# WickedSwitch.net
KiCad netlist of a schematic drawn in EAGLE
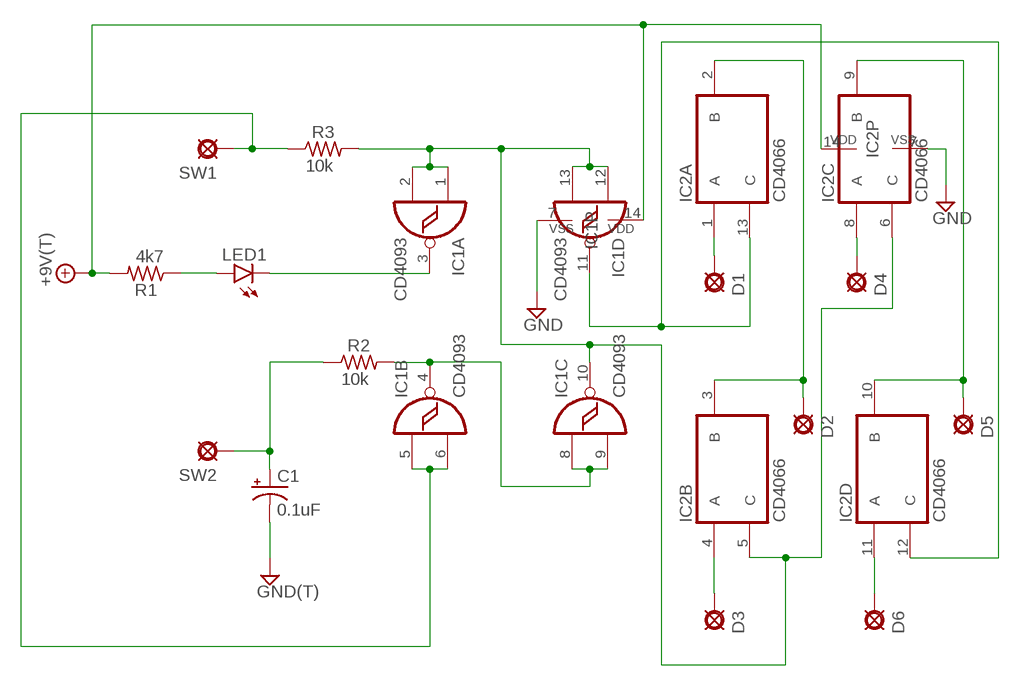
[diagram p0: schematic, sheet 1]

(export (version "E")
  (design (tool "Eeschema 10.0.6"))
  (components
    (comp (ref "+9V")
      (value "+9V(T)")
      (footprint "eagle-import:SQUARE")
      (libsource (lib "eagle-import") (part "+9V(T)"))
    )
    (comp (ref "C1")
      (value "0.1uF")
      (footprint "eagle-import:050_020_1")
      (libsource (lib "eagle-import") (part "0501"))
    )
    (comp (ref "D1")
      (value "1")
      (footprint "eagle-import:ROUND")
      (libsource (lib "eagle-import") (part "PADO"))
    )
    (comp (ref "D2")
      (value "1")
      (footprint "eagle-import:ROUND")
      (libsource (lib "eagle-import") (part "PADO"))
    )
    (comp (ref "D3")
      (value "1")
      (footprint "eagle-import:ROUND")
      (libsource (lib "eagle-import") (part "PADO"))
    )
    (comp (ref "D4")
      (value "1")
      (footprint "eagle-import:ROUND")
      (libsource (lib "eagle-import") (part "PADO"))
    )
    (comp (ref "D5")
      (value "1")
      (footprint "eagle-import:ROUND")
      (libsource (lib "eagle-import") (part "PADO"))
    )
    (comp (ref "D6")
      (value "1")
      (footprint "eagle-import:ROUND")
      (libsource (lib "eagle-import") (part "PADO"))
    )
    (comp (ref "GND")
      (value "GND(T)")
      (footprint "eagle-import:SQUARE")
      (libsource (lib "eagle-import") (part "GND(T)"))
    )
    (comp (ref "IC1")
      (value "CD4093")
      (footprint "eagle-import:DIL14")
      (libsource (lib "eagle-import") (part "4093N"))
    )
    (comp (ref "IC2")
      (value "CD4066")
      (footprint "eagle-import:DIL14")
      (libsource (lib "eagle-import") (part "4066N"))
    )
    (comp (ref "LED1")
      (value "LED3MM")
      (footprint "eagle-import:LED3MM")
      (libsource (lib "eagle-import") (part "LED3MM"))
    )
    (comp (ref "R1")
      (value "4k7")
      (footprint "eagle-import:R0207_3")
      (libsource (lib "eagle-import") (part "6MM.3"))
    )
    (comp (ref "R2")
      (value "10k")
      (footprint "eagle-import:R0207_3")
      (libsource (lib "eagle-import") (part "6MM.3"))
    )
    (comp (ref "R3")
      (value "10k")
      (footprint "eagle-import:R0207_3")
      (libsource (lib "eagle-import") (part "6MM.3"))
    )
    (comp (ref "SW1")
      (value "1")
      (footprint "eagle-import:ROUND")
      (libsource (lib "eagle-import") (part "PADO"))
    )
    (comp (ref "SW2")
      (value "1")
      (footprint "eagle-import:ROUND")
      (libsource (lib "eagle-import") (part "PADO"))
    )
  )
  (nets
    (net (code "1") (name "+9V(T)") (class "Default")
      (node (ref "+9V") (pin "1") (pinfunction "+9V_1") (pintype "power_in"))
      (node (ref "IC1") (pin "14") (pinfunction "VDD_14") (pintype "power_in"))
      (node (ref "IC2") (pin "14") (pinfunction "VDD_14") (pintype "power_in"))
      (node (ref "R1") (pin "2") (pinfunction "2_2") (pintype "passive"))
    )
    (net (code "2") (name "GND") (class "Default")
      (node (ref "C1") (pin "-") (pinfunction "-_-") (pintype "passive"))
      (node (ref "GND") (pin "1") (pinfunction "GND_1") (pintype "power_in"))
      (node (ref "IC1") (pin "7") (pinfunction "VSS_7") (pintype "power_in"))
      (node (ref "IC2") (pin "7") (pinfunction "VSS_7") (pintype "power_in"))
    )
    (net (code "3") (name "Net-(D1-PAD)") (class "Default")
      (node (ref "D1") (pin "1") (pinfunction "PAD_1") (pintype "passive"))
      (node (ref "IC2") (pin "1") (pinfunction "A_1") (pintype "tri_state"))
    )
    (net (code "4") (name "Net-(D2-PAD)") (class "Default")
      (node (ref "D2") (pin "1") (pinfunction "PAD_1") (pintype "passive"))
      (node (ref "IC2") (pin "2") (pinfunction "B_2") (pintype "tri_state"))
      (node (ref "IC2") (pin "3") (pinfunction "B_3") (pintype "tri_state"))
    )
    (net (code "5") (name "Net-(D3-PAD)") (class "Default")
      (node (ref "D3") (pin "1") (pinfunction "PAD_1") (pintype "passive"))
      (node (ref "IC2") (pin "4") (pinfunction "A_4") (pintype "tri_state"))
    )
    (net (code "6") (name "Net-(D4-PAD)") (class "Default")
      (node (ref "D4") (pin "1") (pinfunction "PAD_1") (pintype "passive"))
      (node (ref "IC2") (pin "8") (pinfunction "A_8") (pintype "tri_state"))
    )
    (net (code "7") (name "Net-(D5-PAD)") (class "Default")
      (node (ref "D5") (pin "1") (pinfunction "PAD_1") (pintype "passive"))
      (node (ref "IC2") (pin "10") (pinfunction "B_10") (pintype "tri_state"))
      (node (ref "IC2") (pin "9") (pinfunction "B_9") (pintype "tri_state"))
    )
    (net (code "8") (name "Net-(D6-PAD)") (class "Default")
      (node (ref "D6") (pin "1") (pinfunction "PAD_1") (pintype "passive"))
      (node (ref "IC2") (pin "11") (pinfunction "A_11") (pintype "tri_state"))
    )
    (net (code "9") (name "Net-(IC1A-I0)") (class "Default")
      (node (ref "IC1") (pin "1") (pinfunction "I0_1") (pintype "input"))
      (node (ref "IC1") (pin "10") (pinfunction "O_10") (pintype "output"))
      (node (ref "IC1") (pin "12") (pinfunction "I0_12") (pintype "input"))
      (node (ref "IC1") (pin "13") (pinfunction "I1_13") (pintype "input"))
      (node (ref "IC1") (pin "2") (pinfunction "I1_2") (pintype "input"))
      (node (ref "IC2") (pin "5") (pinfunction "C_5") (pintype "input"))
      (node (ref "IC2") (pin "6") (pinfunction "C_6") (pintype "input"))
      (node (ref "R3") (pin "2") (pinfunction "2_2") (pintype "passive"))
    )
    (net (code "10") (name "Net-(IC1A-O)") (class "Default")
      (node (ref "IC1") (pin "3") (pinfunction "O_3") (pintype "output"))
      (node (ref "LED1") (pin "K") (pinfunction "C_K") (pintype "passive"))
    )
    (net (code "11") (name "Net-(IC1B-I0)") (class "Default")
      (node (ref "IC1") (pin "5") (pinfunction "I0_5") (pintype "input"))
      (node (ref "IC1") (pin "6") (pinfunction "I1_6") (pintype "input"))
      (node (ref "R3") (pin "1") (pinfunction "1_1") (pintype "passive"))
      (node (ref "SW1") (pin "1") (pinfunction "PAD_1") (pintype "passive"))
    )
    (net (code "12") (name "Net-(IC1B-O)") (class "Default")
      (node (ref "IC1") (pin "4") (pinfunction "O_4") (pintype "output"))
      (node (ref "IC1") (pin "8") (pinfunction "I0_8") (pintype "input"))
      (node (ref "IC1") (pin "9") (pinfunction "I1_9") (pintype "input"))
      (node (ref "R2") (pin "2") (pinfunction "2_2") (pintype "passive"))
    )
    (net (code "13") (name "Net-(IC1D-O)") (class "Default")
      (node (ref "IC1") (pin "11") (pinfunction "O_11") (pintype "output"))
      (node (ref "IC2") (pin "12") (pinfunction "C_12") (pintype "input"))
      (node (ref "IC2") (pin "13") (pinfunction "C_13") (pintype "input"))
    )
    (net (code "14") (name "Net-(LED1-PadA)") (class "Default")
      (node (ref "LED1") (pin "A") (pinfunction "A_A") (pintype "passive"))
      (node (ref "R1") (pin "1") (pinfunction "1_1") (pintype "passive"))
    )
    (net (code "15") (name "Net-(SW2-PAD)") (class "Default")
      (node (ref "C1") (pin "+") (pinfunction "+_+") (pintype "passive"))
      (node (ref "R2") (pin "1") (pinfunction "1_1") (pintype "passive"))
      (node (ref "SW2") (pin "1") (pinfunction "PAD_1") (pintype "passive"))
    )
  )
)
